# Regulador.net
KiCad netlist of a schematic drawn in Altium Designer
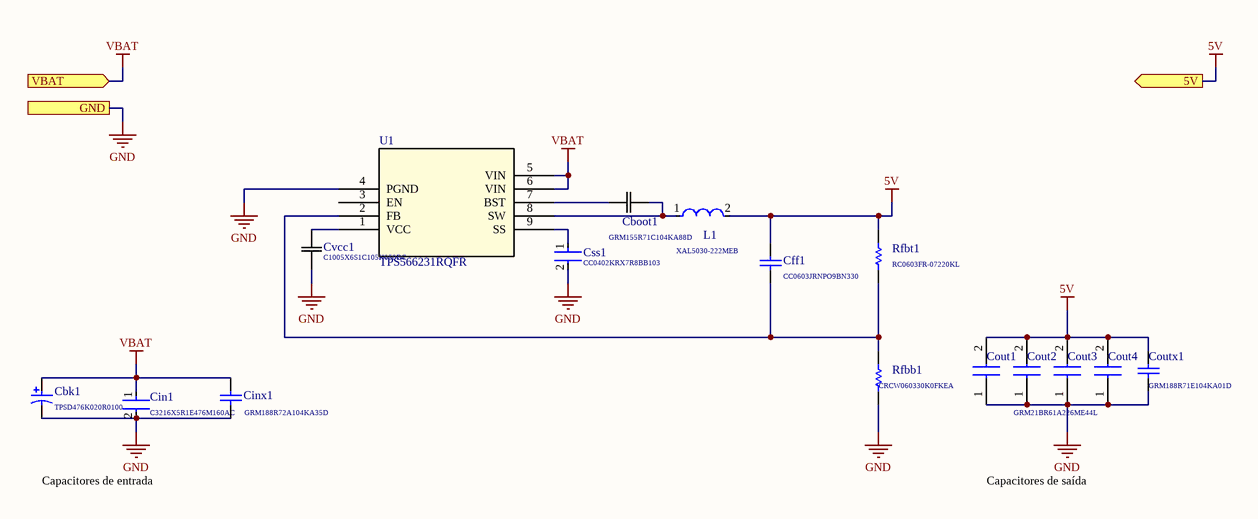
[diagram p0: Regulador.SchDoc]

(export (version "E")
  (design (tool "Eeschema 10.0.6"))
  (components
    (comp (ref "Cbk1")
      (value "TPSD476K020R0100")
      (footprint "TPSD476K020R0100")
      (description "CAP TANT 47UF 20V 10% 2917")
      (fields (field (name "MANUFACTURER") "Kyocera AVX") (field (name "TOLERANCE") "10%"))
      (libsource (lib "Schlib1") (part "TPSD476K020R0100"))
    )
    (comp (ref "Cboot1")
      (value "GRM155R71C104KA88D")
      (footprint "CAP_GRM_155_MUR")
      (description "CAP CER .1UF 16V X7R 0402")
      (fields
        (field (name "DIGIKEYPARTNUMBER") "490-3261-1-ND")
        (field (name "TOLERANCE") "Unknown")
        (field (name "COPYRIGHT") "Copyright (C) 2015 Accelerated Designs. All rights reserved")
      )
      (libsource (lib "GRM155R71C104KA88D") (part "GRM155R71C104KA8"))
    )
    (comp (ref "Cff1")
      (value "CC0603JRNPO9BN330")
      (footprint "CAPC1608X90X40LL10T20")
      (description "Chip Capacitor, 33 pF, +/- 5%, 50 V, -55 to 125 degC, 0603 (1608 Metric), RoHS, Tape and Reel")
      (fields (field (name "MANUFACTURER") "Yageo") (field (name "TOLERANCE") "±5%"))
      (libsource (lib "Altium Content Vault") (part "CAP-NP-2"))
    )
    (comp (ref "Cin1")
      (value "C3216X5R1E476M160AC")
      (footprint "FP-C3216-160-MFG")
      (description "CAP CER 47UF 25V X5R 1206")
      (fields (field (name "3DS PART NUMBER") "220-00004") (field (name "VOLTAGE") "25V"))
      (libsource (lib "Altium Content Vault") (part "11868f565c42a9108669ba33697ecf6"))
    )
    (comp (ref "Cinx1")
      (value "GRM188R72A104KA35D")
      (footprint "CAPC1608X90X35NL10T15")
      (description "Chip Capacitor, 0.1 uF, +/- 10%, 100 V, 0603 (1608 Metric), RoHS, Tape and Reel")
      (fields (field (name "MANUFACTURER") "Murata"))
      (libsource (lib "") (part "CAP-NP-2_1"))
    )
    (comp (ref "Cout1")
      (value "GRM21BR61A226ME44L")
      (footprint "GRM21BR61A226ME44L:CAPC2012X145N")
      (description "Capacitor")
      (fields (field (name "MOUSER PART NUMBER") "81-GRM21BR61A226ME4L"))
      (libsource (lib "GRM21BR61A226ME44L") (part "GRM21BR61A226ME44L"))
    )
    (comp (ref "Cout2")
      (value "GRM21BR61A226ME44L")
      (footprint "GRM21BR61A226ME44L:CAPC2012X145N")
      (description "Capacitor")
      (fields (field (name "MOUSER PART NUMBER") "81-GRM21BR61A226ME4L"))
      (libsource (lib "GRM21BR61A226ME44L") (part "GRM21BR61A226ME44L"))
    )
    (comp (ref "Cout3")
      (value "GRM21BR61A226ME44L")
      (footprint "GRM21BR61A226ME44L:CAPC2012X145N")
      (description "Capacitor")
      (fields (field (name "MOUSER PART NUMBER") "81-GRM21BR61A226ME4L"))
      (libsource (lib "GRM21BR61A226ME44L") (part "GRM21BR61A226ME44L"))
    )
    (comp (ref "Cout4")
      (value "GRM21BR61A226ME44L")
      (footprint "GRM21BR61A226ME44L:CAPC2012X145N")
      (description "Capacitor")
      (fields (field (name "MOUSER PART NUMBER") "81-GRM21BR61A226ME4L"))
      (libsource (lib "GRM21BR61A226ME44L") (part "GRM21BR61A226ME44L"))
    )
    (comp (ref "Coutx1")
      (value "GRM188R71E104KA01D")
      (footprint "CAPC1608X90X35LL10T15")
      (fields (field (name "MANUFACTURER") "Murata"))
      (libsource (lib "Altium Content Vault") (part "CAP"))
    )
    (comp (ref "Css1")
      (value "CC0402KRX7R8BB103")
      (footprint "FP-CC0402-MFG")
      (description "CAP CER 10000PF 25V X7R 0402")
      (fields
        (field (name "OCTOPART") "https://octopart.com/cc0402krx7r8bb103-yageo-8376512")
        (field (name "MANUFACTURER") "YAGEO")
      )
      (libsource (lib "Altium Content Vault") (part "11868f565c42a9108669ba33697ecf6"))
    )
    (comp (ref "Cvcc1")
      (value "C1005X6S1C105K050BC")
      (footprint "CAP_1005_TDK")
      (description "No Description Available")
      (fields (field (name "COPYRIGHT") "Copyright (C) 2018 Accelerated Designs. All rights reserved"))
      (libsource (lib "C1005X6S1C105K050BC") (part "C1005X6S1C105K05"))
    )
    (comp (ref "L1")
      (value "XAL5030-222MEB")
      (footprint "FP-XAL5030-222MEB-MFG")
      (description "Fixed Inductors 2.2uH 20% 9.7A 14.5mOhms")
      (fields (field (name "TOLERANCE") "20%"))
      (libsource (lib "Altium Content Vault") (part "725321dda6339637d4d059423bc1c3c"))
    )
    (comp (ref "Rfbb1")
      (value "CRCW060330K0FKEA")
      (footprint "RESC1609X50X30LL10T20")
      (fields (field (name "MANUFACTURER") "Vishay Dale"))
      (libsource (lib "Altium Content Vault") (part "RES"))
    )
    (comp (ref "Rfbt1")
      (value "RC0603FR-07220KL")
      (footprint "RESC1608X55X25ML10T15")
      (description "Chip Resistor, 220 KOhm, +/- 1%, 100 mW, -55 to 155 degC, 0603 (1608 Metric), RoHS, Tape and Reel")
      (libsource (lib "Altium Content Vault") (part "RES-2"))
    )
    (comp (ref "U1")
      (value "TPS566231RQFR")
      (footprint "QFN_231RQFR_TEX")
      (description "No Description Available")
      (fields (field (name "COPYRIGHT") "Copyright (C) 2018 Accelerated Designs. All rights reserved"))
      (libsource (lib "TPS566231RQF") (part "TPS566231RQFR"))
    )
  )
  (nets
    (net (code "1") (name "5V") (class "Default")
      (node (ref "Cff1") (pin "2") (pinfunction "2_2") (pintype "passive"))
      (node (ref "Cout1") (pin "2") (pinfunction "2_2") (pintype "passive"))
      (node (ref "Cout2") (pin "2") (pinfunction "2_2") (pintype "passive"))
      (node (ref "Cout3") (pin "2") (pinfunction "2_2") (pintype "passive"))
      (node (ref "Cout4") (pin "2") (pinfunction "2_2") (pintype "passive"))
      (node (ref "Coutx1") (pin "2") (pinfunction "2_2") (pintype "passive"))
      (node (ref "L1") (pin "2") (pinfunction "2_2") (pintype "passive"))
      (node (ref "Rfbt1") (pin "2") (pinfunction "2_2") (pintype "passive"))
    )
    (net (code "2") (name "GND") (class "Default")
      (node (ref "Cbk1") (pin "2") (pinfunction "2_2") (pintype "passive"))
      (node (ref "Cin1") (pin "2") (pinfunction "2_2") (pintype "passive"))
      (node (ref "Cinx1") (pin "1") (pinfunction "1_1") (pintype "passive"))
      (node (ref "Cout1") (pin "1") (pinfunction "1_1") (pintype "passive"))
      (node (ref "Cout2") (pin "1") (pinfunction "1_1") (pintype "passive"))
      (node (ref "Cout3") (pin "1") (pinfunction "1_1") (pintype "passive"))
      (node (ref "Cout4") (pin "1") (pinfunction "1_1") (pintype "passive"))
      (node (ref "Coutx1") (pin "1") (pinfunction "1_1") (pintype "passive"))
      (node (ref "Css1") (pin "2") (pinfunction "2_2") (pintype "passive"))
      (node (ref "Cvcc1") (pin "2") (pinfunction "2_2") (pintype "passive"))
      (node (ref "Rfbb1") (pin "1") (pinfunction "1_1") (pintype "passive"))
      (node (ref "U1") (pin "4") (pinfunction "PGND_4") (pintype "passive"))
    )
    (net (code "3") (name "Net-(U1-BST)") (class "Default")
      (node (ref "Cboot1") (pin "2") (pinfunction "2_2") (pintype "passive"))
      (node (ref "U1") (pin "7") (pinfunction "BST_7") (pintype "passive"))
    )
    (net (code "4") (name "Net-(U1-FB)") (class "Default")
      (node (ref "Cff1") (pin "1") (pinfunction "1_1") (pintype "passive"))
      (node (ref "Rfbb1") (pin "2") (pinfunction "2_2") (pintype "passive"))
      (node (ref "Rfbt1") (pin "1") (pinfunction "1_1") (pintype "passive"))
      (node (ref "U1") (pin "2") (pinfunction "FB_2") (pintype "passive"))
    )
    (net (code "5") (name "Net-(U1-SS)") (class "Default")
      (node (ref "Css1") (pin "1") (pinfunction "1_1") (pintype "passive"))
      (node (ref "U1") (pin "9") (pinfunction "SS_9") (pintype "passive"))
    )
    (net (code "6") (name "Net-(U1-SW)") (class "Default")
      (node (ref "Cboot1") (pin "1") (pinfunction "1_1") (pintype "passive"))
      (node (ref "L1") (pin "1") (pinfunction "1_1") (pintype "passive"))
      (node (ref "U1") (pin "8") (pinfunction "SW_8") (pintype "passive"))
    )
    (net (code "7") (name "Net-(U1-VCC)") (class "Default")
      (node (ref "Cvcc1") (pin "1") (pinfunction "1_1") (pintype "passive"))
      (node (ref "U1") (pin "1") (pinfunction "VCC_1") (pintype "power_in"))
    )
    (net (code "8") (name "VBAT") (class "Default")
      (node (ref "Cbk1") (pin "1") (pinfunction "1_1") (pintype "passive"))
      (node (ref "Cin1") (pin "1") (pinfunction "1_1") (pintype "passive"))
      (node (ref "Cinx1") (pin "2") (pinfunction "2_2") (pintype "passive"))
      (node (ref "U1") (pin "5") (pinfunction "VIN_5") (pintype "passive"))
      (node (ref "U1") (pin "6") (pinfunction "VIN_6") (pintype "passive"))
    )
    (net (code "9") (name "unconnected-(U1-EN-Pad3)") (class "Default")
      (node (ref "U1") (pin "3") (pinfunction "EN_3") (pintype "passive"))
    )
  )
)
